# sensor.net
KiCad netlist of a schematic drawn in EAGLE
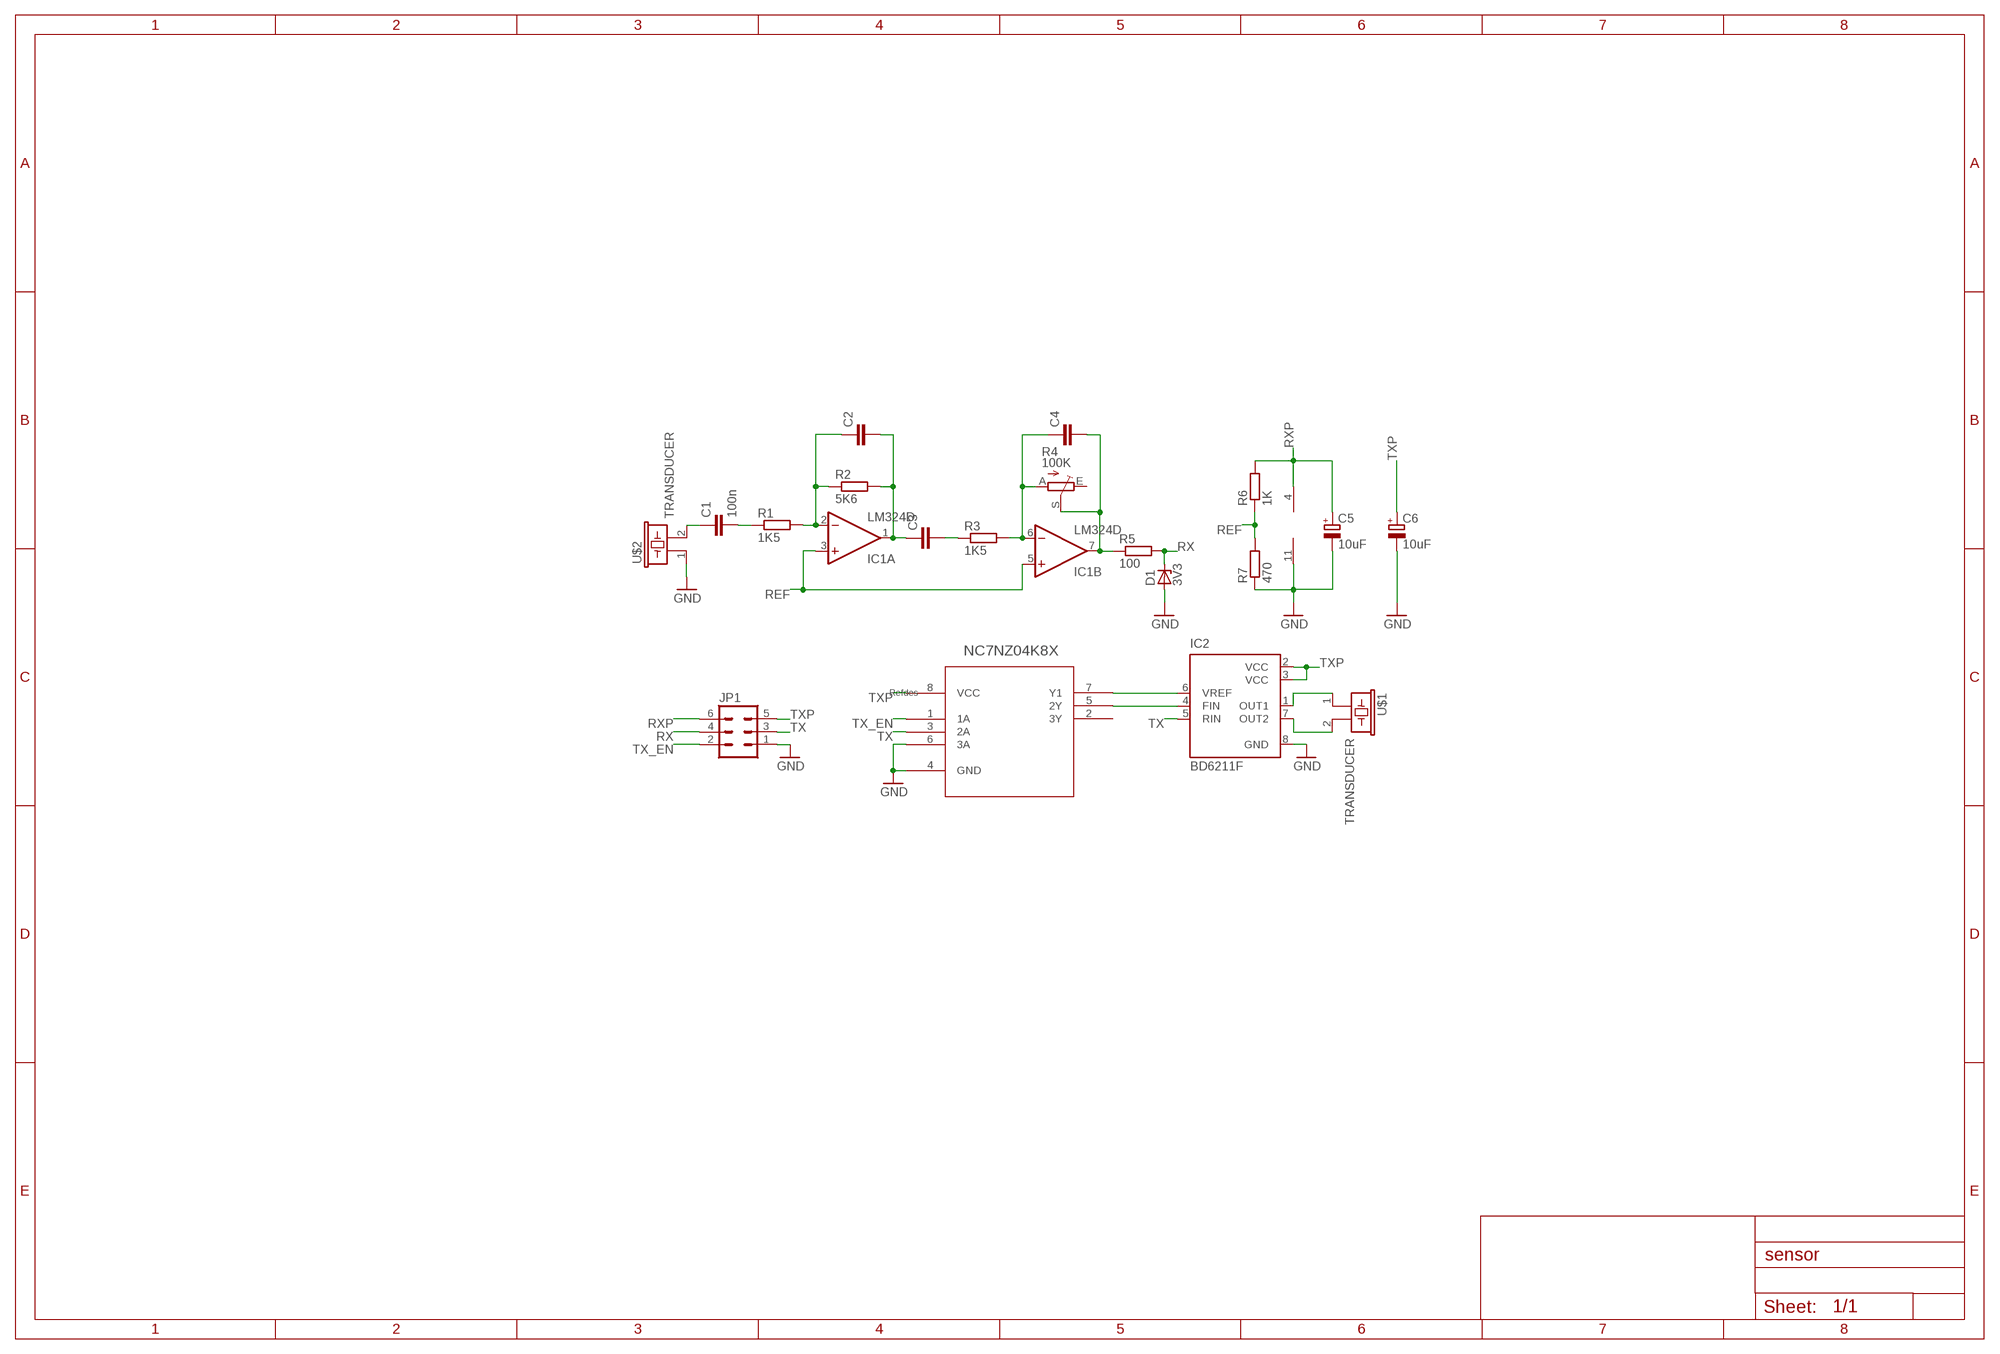
[diagram p0: schematic, sheet 1]

(export (version "E")
  (design (tool "Eeschema 10.0.6"))
  (components
    (comp (ref "C1")
      (value "100n")
      (footprint "eagle-import:C0805")
      (libsource (lib "eagle-import") (part "C-EUC0805"))
    )
    (comp (ref "C2")
      (value "C-EUC0805")
      (footprint "eagle-import:C0805")
      (libsource (lib "eagle-import") (part "C-EUC0805"))
    )
    (comp (ref "C3")
      (value "C-EUC0805")
      (footprint "eagle-import:C0805")
      (libsource (lib "eagle-import") (part "C-EUC0805"))
    )
    (comp (ref "C4")
      (value "C-EUC0805")
      (footprint "eagle-import:C0805")
      (libsource (lib "eagle-import") (part "C-EUC0805"))
    )
    (comp (ref "C5")
      (value "10uF")
      (footprint "eagle-import:E2-5")
      (libsource (lib "eagle-import") (part "CPOL-EUE2-5"))
    )
    (comp (ref "C6")
      (value "10uF")
      (footprint "eagle-import:E2-5")
      (libsource (lib "eagle-import") (part "CPOL-EUE2-5"))
    )
    (comp (ref "D1")
      (value "3V3")
      (footprint "eagle-import:ZDIO-2.5")
      (libsource (lib "eagle-import") (part "ZENER-DIODEZD-2.5"))
    )
    (comp (ref "IC1")
      (value "LM324D")
      (footprint "eagle-import:SO14")
      (fields (field (name "OC_FARNELL") "1426353"))
      (libsource (lib "eagle-import") (part "LM324D"))
    )
    (comp (ref "IC2")
      (value "BD6211F")
      (footprint "eagle-import:SOP8")
      (libsource (lib "eagle-import") (part "BD6211F"))
    )
    (comp (ref "JP1")
      (value "MA03-2")
      (footprint "eagle-import:MA03-2")
      (libsource (lib "eagle-import") (part "MA03-2"))
    )
    (comp (ref "R1")
      (value "1K5")
      (footprint "eagle-import:R0805")
      (libsource (lib "eagle-import") (part "R-EU_R0805"))
    )
    (comp (ref "R2")
      (value "5K6")
      (footprint "eagle-import:R0805")
      (libsource (lib "eagle-import") (part "R-EU_R0805"))
    )
    (comp (ref "R3")
      (value "1K5")
      (footprint "eagle-import:R0805")
      (libsource (lib "eagle-import") (part "R-EU_R0805"))
    )
    (comp (ref "R4")
      (value "100K")
      (footprint "eagle-import:S63P")
      (libsource (lib "eagle-import") (part "TRIM_EU-S63P"))
    )
    (comp (ref "R5")
      (value "100")
      (footprint "eagle-import:R0805")
      (libsource (lib "eagle-import") (part "R-EU_R0805"))
    )
    (comp (ref "R6")
      (value "1K")
      (footprint "eagle-import:R0805")
      (libsource (lib "eagle-import") (part "R-EU_R0805"))
    )
    (comp (ref "R7")
      (value "470")
      (footprint "eagle-import:R0805")
      (libsource (lib "eagle-import") (part "R-EU_R0805"))
    )
    (comp (ref "U$1")
      (value "TRANSDUCER")
      (footprint "eagle-import:TRANSDUCER")
      (libsource (lib "eagle-import") (part "TRANSDUCER"))
    )
    (comp (ref "U$2")
      (value "TRANSDUCER")
      (footprint "eagle-import:TRANSDUCER")
      (libsource (lib "eagle-import") (part "TRANSDUCER"))
    )
    (comp (ref "U1")
      (value "NC7NZ04K8X")
      (footprint "eagle-import:SOP50P310X90-8N")
      (libsource (lib "eagle-import") (part "NC7NZ04K8X"))
    )
  )
  (nets
    (net (code "1") (name "/REF") (class "Default")
      (node (ref "IC1") (pin "3") (pinfunction "+IN_3") (pintype "input"))
      (node (ref "IC1") (pin "5") (pinfunction "+IN_5") (pintype "input"))
      (node (ref "R6") (pin "1") (pinfunction "1_1") (pintype "passive"))
      (node (ref "R7") (pin "2") (pinfunction "2_2") (pintype "passive"))
    )
    (net (code "2") (name "/RX") (class "Default")
      (node (ref "D1") (pin "C") (pinfunction "C_C") (pintype "passive"))
      (node (ref "JP1") (pin "4") (pinfunction "4_4") (pintype "passive"))
      (node (ref "R5") (pin "2") (pinfunction "2_2") (pintype "passive"))
    )
    (net (code "3") (name "/RXP") (class "Default")
      (node (ref "C5") (pin "+") (pinfunction "+_+") (pintype "passive"))
      (node (ref "IC1") (pin "4") (pinfunction "V+_4") (pintype "power_in"))
      (node (ref "JP1") (pin "6") (pinfunction "6_6") (pintype "passive"))
      (node (ref "R6") (pin "2") (pinfunction "2_2") (pintype "passive"))
    )
    (net (code "4") (name "/TX") (class "Default")
      (node (ref "IC2") (pin "5") (pinfunction "RIN_5") (pintype "input"))
      (node (ref "JP1") (pin "3") (pinfunction "3_3") (pintype "passive"))
      (node (ref "U1") (pin "3") (pinfunction "2A_3") (pintype "input"))
    )
    (net (code "5") (name "/TXP") (class "Default")
      (node (ref "C6") (pin "+") (pinfunction "+_+") (pintype "passive"))
      (node (ref "IC2") (pin "2") (pinfunction "VCC_2") (pintype "power_in"))
      (node (ref "IC2") (pin "3") (pinfunction "VCC_3") (pintype "power_in"))
      (node (ref "JP1") (pin "5") (pinfunction "5_5") (pintype "passive"))
      (node (ref "U1") (pin "8") (pinfunction "VCC_8") (pintype "power_in"))
    )
    (net (code "6") (name "/TX_EN") (class "Default")
      (node (ref "JP1") (pin "2") (pinfunction "2_2") (pintype "passive"))
      (node (ref "U1") (pin "1") (pinfunction "1A_1") (pintype "input"))
    )
    (net (code "7") (name "GND") (class "Default")
      (node (ref "C5") (pin "-") (pinfunction "-_-") (pintype "passive"))
      (node (ref "C6") (pin "-") (pinfunction "-_-") (pintype "passive"))
      (node (ref "D1") (pin "A") (pinfunction "A_A") (pintype "passive"))
      (node (ref "IC1") (pin "11") (pinfunction "V-_11") (pintype "power_in"))
      (node (ref "IC2") (pin "8") (pinfunction "GND_8") (pintype "power_in"))
      (node (ref "JP1") (pin "1") (pinfunction "1_1") (pintype "passive"))
      (node (ref "R7") (pin "1") (pinfunction "1_1") (pintype "passive"))
      (node (ref "U$2") (pin "1") (pinfunction "1_1") (pintype "passive"))
      (node (ref "U1") (pin "4") (pinfunction "GND_4") (pintype "passive"))
      (node (ref "U1") (pin "6") (pinfunction "3A_6") (pintype "input"))
    )
    (net (code "8") (name "Net-(C1-Pad1)") (class "Default")
      (node (ref "C1") (pin "1") (pinfunction "1_1") (pintype "passive"))
      (node (ref "U$2") (pin "2") (pinfunction "2_2") (pintype "passive"))
    )
    (net (code "9") (name "Net-(C1-Pad2)") (class "Default")
      (node (ref "C1") (pin "2") (pinfunction "2_2") (pintype "passive"))
      (node (ref "R1") (pin "1") (pinfunction "1_1") (pintype "passive"))
    )
    (net (code "10") (name "Net-(C3-Pad2)") (class "Default")
      (node (ref "C3") (pin "2") (pinfunction "2_2") (pintype "passive"))
      (node (ref "R3") (pin "1") (pinfunction "1_1") (pintype "passive"))
    )
    (net (code "11") (name "Net-(IC1A--IN)") (class "Default")
      (node (ref "C2") (pin "1") (pinfunction "1_1") (pintype "passive"))
      (node (ref "IC1") (pin "2") (pinfunction "-IN_2") (pintype "input"))
      (node (ref "R1") (pin "2") (pinfunction "2_2") (pintype "passive"))
      (node (ref "R2") (pin "1") (pinfunction "1_1") (pintype "passive"))
    )
    (net (code "12") (name "Net-(IC1A-OUT)") (class "Default")
      (node (ref "C2") (pin "2") (pinfunction "2_2") (pintype "passive"))
      (node (ref "C3") (pin "1") (pinfunction "1_1") (pintype "passive"))
      (node (ref "IC1") (pin "1") (pinfunction "OUT_1") (pintype "output"))
      (node (ref "R2") (pin "2") (pinfunction "2_2") (pintype "passive"))
    )
    (net (code "13") (name "Net-(IC1B--IN)") (class "Default")
      (node (ref "C4") (pin "1") (pinfunction "1_1") (pintype "passive"))
      (node (ref "IC1") (pin "6") (pinfunction "-IN_6") (pintype "input"))
      (node (ref "R3") (pin "2") (pinfunction "2_2") (pintype "passive"))
      (node (ref "R4") (pin "A") (pinfunction "A_A") (pintype "passive"))
    )
    (net (code "14") (name "Net-(IC1B-OUT)") (class "Default")
      (node (ref "C4") (pin "2") (pinfunction "2_2") (pintype "passive"))
      (node (ref "IC1") (pin "7") (pinfunction "OUT_7") (pintype "output"))
      (node (ref "R4") (pin "S") (pinfunction "S_S") (pintype "passive"))
      (node (ref "R5") (pin "1") (pinfunction "1_1") (pintype "passive"))
    )
    (net (code "15") (name "Net-(IC2-FIN)") (class "Default")
      (node (ref "IC2") (pin "4") (pinfunction "FIN_4") (pintype "input"))
      (node (ref "U1") (pin "5") (pinfunction "2Y_5") (pintype "output"))
    )
    (net (code "16") (name "Net-(IC2-OUT1)") (class "Default")
      (node (ref "IC2") (pin "1") (pinfunction "OUT1_1") (pintype "output"))
      (node (ref "U$1") (pin "1") (pinfunction "1_1") (pintype "passive"))
    )
    (net (code "17") (name "Net-(IC2-OUT2)") (class "Default")
      (node (ref "IC2") (pin "7") (pinfunction "OUT2_7") (pintype "output"))
      (node (ref "U$1") (pin "2") (pinfunction "2_2") (pintype "passive"))
    )
    (net (code "18") (name "Net-(IC2-VREF)") (class "Default")
      (node (ref "IC2") (pin "6") (pinfunction "VREF_6") (pintype "passive"))
      (node (ref "U1") (pin "7") (pinfunction "Y1_7") (pintype "output"))
    )
    (net (code "19") (name "unconnected-(R4-PadE)") (class "Default")
      (node (ref "R4") (pin "E") (pinfunction "E_E") (pintype "passive"))
    )
    (net (code "20") (name "unconnected-(U1-3Y-Pad2)") (class "Default")
      (node (ref "U1") (pin "2") (pinfunction "3Y_2") (pintype "output"))
    )
  )
)
